# BYPASS_CAP.net
KiCad netlist of a schematic drawn in Altium Designer
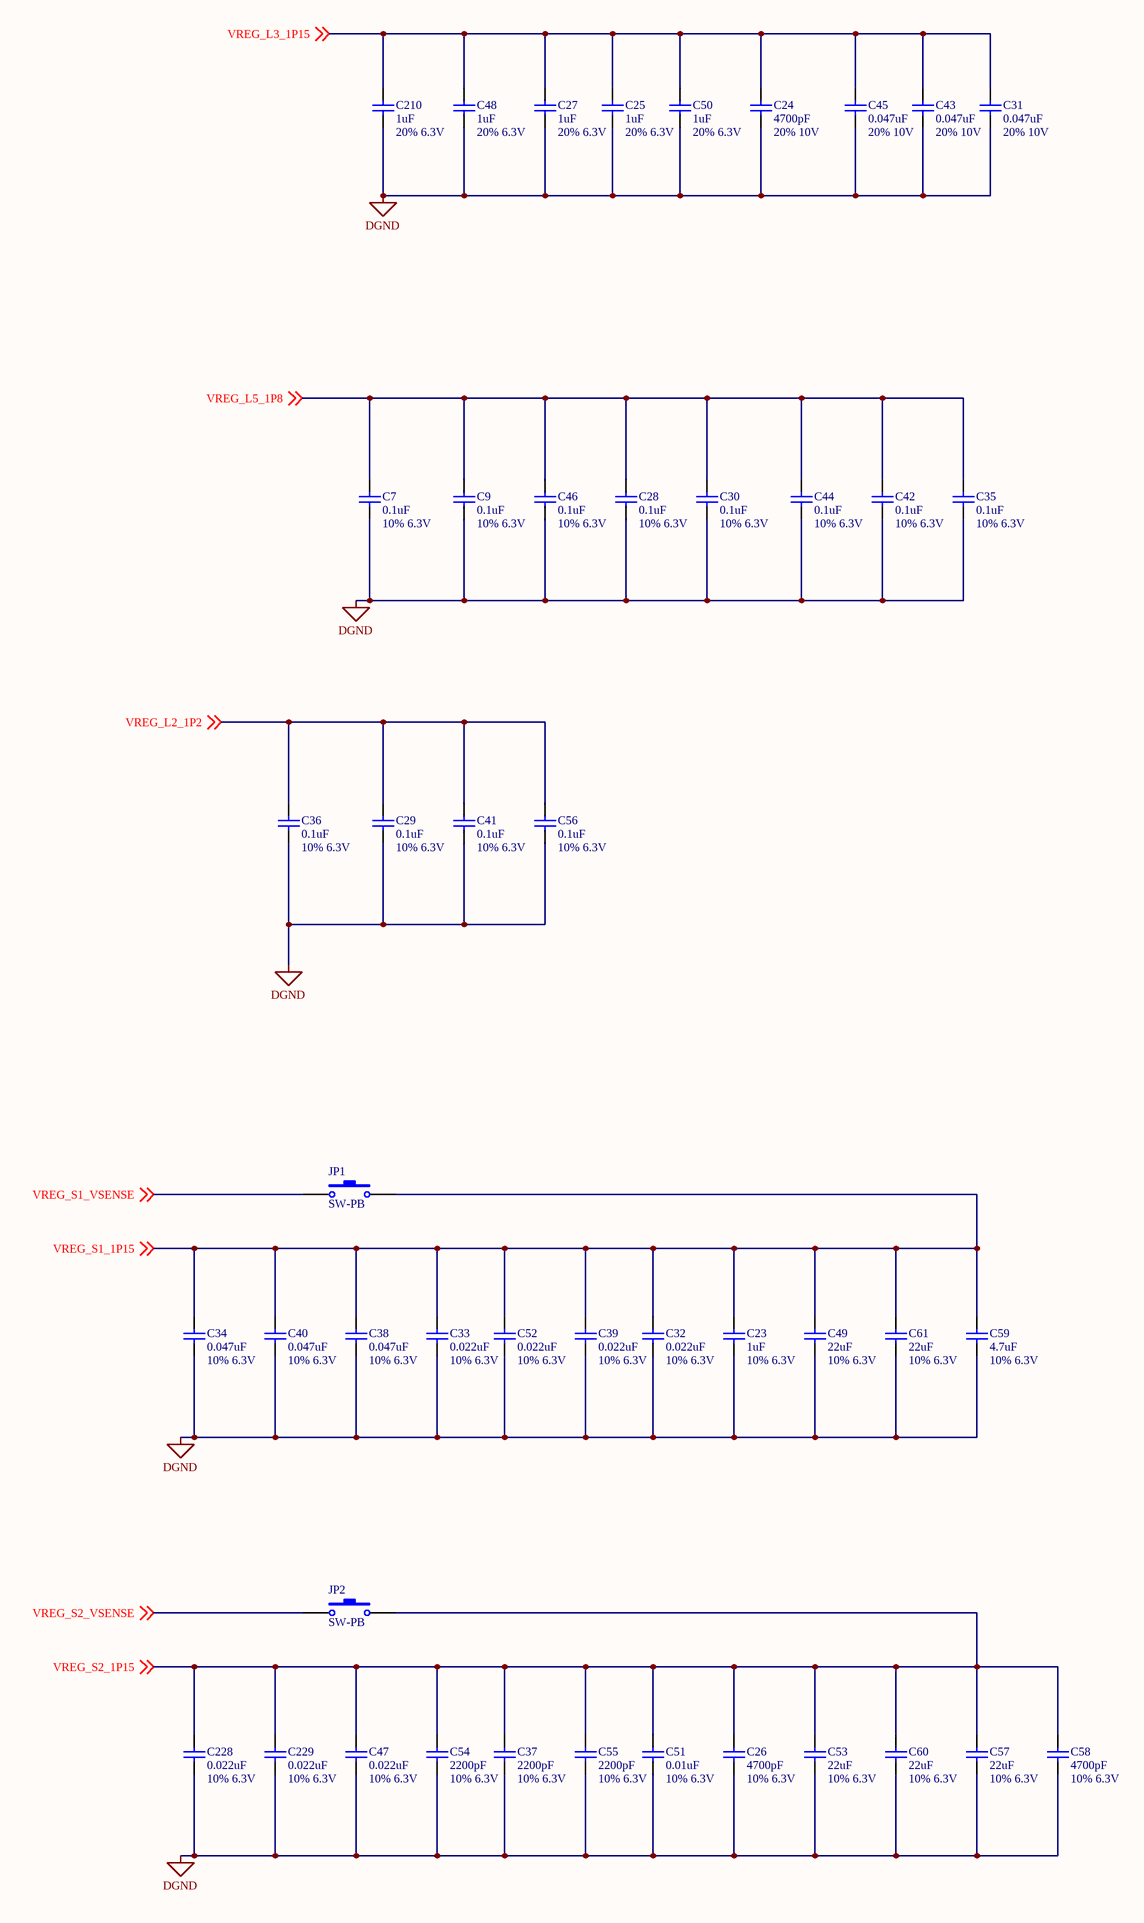
[diagram p0: BYPASS_CAP.SchDoc]

(export (version "E")
  (design (tool "Eeschema 10.0.6"))
  (components
    (comp (ref "C7")
      (value "0.1uF")
      (footprint "C0402")
      (description "Capacitor")
      (fields (field (name "ALTIUM_VALUE") "10% 6.3V") (field (name "PUBLISHER") "Altium Limited"))
      (libsource (lib "Miscellaneous Devices") (part "Cap"))
    )
    (comp (ref "C9")
      (value "0.1uF")
      (footprint "C0402")
      (description "Capacitor")
      (fields (field (name "ALTIUM_VALUE") "10% 6.3V") (field (name "PUBLISHER") "Altium Limited"))
      (libsource (lib "Miscellaneous Devices") (part "Cap"))
    )
    (comp (ref "C23")
      (value "1uF")
      (footprint "C0402")
      (description "Capacitor")
      (fields (field (name "ALTIUM_VALUE") "10% 6.3V") (field (name "PUBLISHER") "Altium Limited"))
      (libsource (lib "Miscellaneous Devices") (part "Cap"))
    )
    (comp (ref "C24")
      (value "4700pF")
      (footprint "C0402")
      (description "Capacitor")
      (fields (field (name "ALTIUM_VALUE") "20% 10V") (field (name "PUBLISHER") "Altium Limited"))
      (libsource (lib "Miscellaneous Devices") (part "Cap"))
    )
    (comp (ref "C25")
      (value "1uF")
      (footprint "C0402")
      (description "Capacitor")
      (fields (field (name "ALTIUM_VALUE") "20% 6.3V") (field (name "PUBLISHER") "Altium Limited"))
      (libsource (lib "Miscellaneous Devices") (part "Cap"))
    )
    (comp (ref "C26")
      (value "4700pF")
      (footprint "C0402")
      (description "Capacitor")
      (fields (field (name "ALTIUM_VALUE") "10% 6.3V") (field (name "PUBLISHER") "Altium Limited"))
      (libsource (lib "Miscellaneous Devices") (part "Cap"))
    )
    (comp (ref "C27")
      (value "1uF")
      (footprint "C0402")
      (description "Capacitor")
      (fields (field (name "ALTIUM_VALUE") "20% 6.3V") (field (name "PUBLISHER") "Altium Limited"))
      (libsource (lib "Miscellaneous Devices") (part "Cap"))
    )
    (comp (ref "C28")
      (value "0.1uF")
      (footprint "C0402")
      (description "Capacitor")
      (fields (field (name "ALTIUM_VALUE") "10% 6.3V") (field (name "PUBLISHER") "Altium Limited"))
      (libsource (lib "Miscellaneous Devices") (part "Cap"))
    )
    (comp (ref "C29")
      (value "0.1uF")
      (footprint "C0402")
      (description "Capacitor")
      (fields (field (name "ALTIUM_VALUE") "10% 6.3V") (field (name "PUBLISHER") "Altium Limited"))
      (libsource (lib "Miscellaneous Devices") (part "Cap"))
    )
    (comp (ref "C30")
      (value "0.1uF")
      (footprint "C0402")
      (description "Capacitor")
      (fields (field (name "ALTIUM_VALUE") "10% 6.3V") (field (name "PUBLISHER") "Altium Limited"))
      (libsource (lib "Miscellaneous Devices") (part "Cap"))
    )
    (comp (ref "C31")
      (value "0.047uF")
      (footprint "C0402")
      (description "Capacitor")
      (fields (field (name "ALTIUM_VALUE") "20% 10V") (field (name "PUBLISHER") "Altium Limited"))
      (libsource (lib "Miscellaneous Devices") (part "Cap"))
    )
    (comp (ref "C32")
      (value "0.022uF")
      (footprint "C0402")
      (description "Capacitor")
      (fields (field (name "ALTIUM_VALUE") "10% 6.3V") (field (name "PUBLISHER") "Altium Limited"))
      (libsource (lib "Miscellaneous Devices") (part "Cap"))
    )
    (comp (ref "C33")
      (value "0.022uF")
      (footprint "C0402")
      (description "Capacitor")
      (fields (field (name "ALTIUM_VALUE") "10% 6.3V") (field (name "PUBLISHER") "Altium Limited"))
      (libsource (lib "Miscellaneous Devices") (part "Cap"))
    )
    (comp (ref "C34")
      (value "0.047uF")
      (footprint "C0402")
      (description "Capacitor")
      (fields (field (name "ALTIUM_VALUE") "10% 6.3V") (field (name "PUBLISHER") "Altium Limited"))
      (libsource (lib "Miscellaneous Devices") (part "Cap"))
    )
    (comp (ref "C35")
      (value "0.1uF")
      (footprint "C0402")
      (description "Capacitor")
      (fields (field (name "ALTIUM_VALUE") "10% 6.3V") (field (name "PUBLISHER") "Altium Limited"))
      (libsource (lib "Miscellaneous Devices") (part "Cap"))
    )
    (comp (ref "C36")
      (value "0.1uF")
      (footprint "C0402")
      (description "Capacitor")
      (fields (field (name "ALTIUM_VALUE") "10% 6.3V") (field (name "PUBLISHER") "Altium Limited"))
      (libsource (lib "Miscellaneous Devices") (part "Cap"))
    )
    (comp (ref "C37")
      (value "2200pF")
      (footprint "C0402")
      (description "Capacitor")
      (fields (field (name "ALTIUM_VALUE") "10% 6.3V") (field (name "PUBLISHER") "Altium Limited"))
      (libsource (lib "Miscellaneous Devices") (part "Cap"))
    )
    (comp (ref "C38")
      (value "0.047uF")
      (footprint "C0402")
      (description "Capacitor")
      (fields (field (name "ALTIUM_VALUE") "10% 6.3V") (field (name "PUBLISHER") "Altium Limited"))
      (libsource (lib "Miscellaneous Devices") (part "Cap"))
    )
    (comp (ref "C39")
      (value "0.022uF")
      (footprint "C0402")
      (description "Capacitor")
      (fields (field (name "ALTIUM_VALUE") "10% 6.3V") (field (name "PUBLISHER") "Altium Limited"))
      (libsource (lib "Miscellaneous Devices") (part "Cap"))
    )
    (comp (ref "C40")
      (value "0.047uF")
      (footprint "C0402")
      (description "Capacitor")
      (fields (field (name "ALTIUM_VALUE") "10% 6.3V") (field (name "PUBLISHER") "Altium Limited"))
      (libsource (lib "Miscellaneous Devices") (part "Cap"))
    )
    (comp (ref "C41")
      (value "0.1uF")
      (footprint "C0402")
      (description "Capacitor")
      (fields (field (name "ALTIUM_VALUE") "10% 6.3V") (field (name "PUBLISHER") "Altium Limited"))
      (libsource (lib "Miscellaneous Devices") (part "Cap"))
    )
    (comp (ref "C42")
      (value "0.1uF")
      (footprint "C0402")
      (description "Capacitor")
      (fields (field (name "ALTIUM_VALUE") "10% 6.3V") (field (name "PUBLISHER") "Altium Limited"))
      (libsource (lib "Miscellaneous Devices") (part "Cap"))
    )
    (comp (ref "C43")
      (value "0.047uF")
      (footprint "C0402")
      (description "Capacitor")
      (fields (field (name "ALTIUM_VALUE") "20% 10V") (field (name "PUBLISHER") "Altium Limited"))
      (libsource (lib "Miscellaneous Devices") (part "Cap"))
    )
    (comp (ref "C44")
      (value "0.1uF")
      (footprint "C0402")
      (description "Capacitor")
      (fields (field (name "ALTIUM_VALUE") "10% 6.3V") (field (name "PUBLISHER") "Altium Limited"))
      (libsource (lib "Miscellaneous Devices") (part "Cap"))
    )
    (comp (ref "C45")
      (value "0.047uF")
      (footprint "C0402")
      (description "Capacitor")
      (fields (field (name "ALTIUM_VALUE") "20% 10V") (field (name "PUBLISHER") "Altium Limited"))
      (libsource (lib "Miscellaneous Devices") (part "Cap"))
    )
    (comp (ref "C46")
      (value "0.1uF")
      (footprint "C0402")
      (description "Capacitor")
      (fields (field (name "ALTIUM_VALUE") "10% 6.3V") (field (name "PUBLISHER") "Altium Limited"))
      (libsource (lib "Miscellaneous Devices") (part "Cap"))
    )
    (comp (ref "C47")
      (value "0.022uF")
      (footprint "C0402")
      (description "Capacitor")
      (fields (field (name "ALTIUM_VALUE") "10% 6.3V") (field (name "PUBLISHER") "Altium Limited"))
      (libsource (lib "Miscellaneous Devices") (part "Cap"))
    )
    (comp (ref "C48")
      (value "1uF")
      (footprint "C0402")
      (description "Capacitor")
      (fields (field (name "ALTIUM_VALUE") "20% 6.3V") (field (name "PUBLISHER") "Altium Limited"))
      (libsource (lib "Miscellaneous Devices") (part "Cap"))
    )
    (comp (ref "C49")
      (value "22uF")
      (footprint "C0402")
      (description "Capacitor")
      (fields (field (name "ALTIUM_VALUE") "10% 6.3V") (field (name "PUBLISHER") "Altium Limited"))
      (libsource (lib "Miscellaneous Devices") (part "Cap"))
    )
    (comp (ref "C50")
      (value "1uF")
      (footprint "C0402")
      (description "Capacitor")
      (fields (field (name "ALTIUM_VALUE") "20% 6.3V") (field (name "PUBLISHER") "Altium Limited"))
      (libsource (lib "Miscellaneous Devices") (part "Cap"))
    )
    (comp (ref "C51")
      (value "0.01uF")
      (footprint "C0402")
      (description "Capacitor")
      (fields (field (name "ALTIUM_VALUE") "10% 6.3V") (field (name "PUBLISHER") "Altium Limited"))
      (libsource (lib "Miscellaneous Devices") (part "Cap"))
    )
    (comp (ref "C52")
      (value "0.022uF")
      (footprint "C0402")
      (description "Capacitor")
      (fields (field (name "ALTIUM_VALUE") "10% 6.3V") (field (name "PUBLISHER") "Altium Limited"))
      (libsource (lib "Miscellaneous Devices") (part "Cap"))
    )
    (comp (ref "C53")
      (value "22uF")
      (footprint "C0402")
      (description "Capacitor")
      (fields (field (name "ALTIUM_VALUE") "10% 6.3V") (field (name "PUBLISHER") "Altium Limited"))
      (libsource (lib "Miscellaneous Devices") (part "Cap"))
    )
    (comp (ref "C54")
      (value "2200pF")
      (footprint "C0402")
      (description "Capacitor")
      (fields (field (name "ALTIUM_VALUE") "10% 6.3V") (field (name "PUBLISHER") "Altium Limited"))
      (libsource (lib "Miscellaneous Devices") (part "Cap"))
    )
    (comp (ref "C55")
      (value "2200pF")
      (footprint "C0402")
      (description "Capacitor")
      (fields (field (name "ALTIUM_VALUE") "10% 6.3V") (field (name "PUBLISHER") "Altium Limited"))
      (libsource (lib "Miscellaneous Devices") (part "Cap"))
    )
    (comp (ref "C56")
      (value "0.1uF")
      (footprint "C0402")
      (description "Capacitor")
      (fields (field (name "ALTIUM_VALUE") "10% 6.3V") (field (name "PUBLISHER") "Altium Limited"))
      (libsource (lib "Miscellaneous Devices") (part "Cap"))
    )
    (comp (ref "C57")
      (value "22uF")
      (footprint "C0402")
      (description "Capacitor")
      (fields (field (name "ALTIUM_VALUE") "10% 6.3V") (field (name "PUBLISHER") "Altium Limited"))
      (libsource (lib "Miscellaneous Devices") (part "Cap"))
    )
    (comp (ref "C58")
      (value "4700pF")
      (footprint "C0402")
      (description "Capacitor")
      (fields (field (name "ALTIUM_VALUE") "10% 6.3V") (field (name "PUBLISHER") "Altium Limited"))
      (libsource (lib "Miscellaneous Devices") (part "Cap"))
    )
    (comp (ref "C59")
      (value "4.7uF")
      (footprint "C0402")
      (description "Capacitor")
      (fields (field (name "ALTIUM_VALUE") "10% 6.3V") (field (name "PUBLISHER") "Altium Limited"))
      (libsource (lib "Miscellaneous Devices") (part "Cap"))
    )
    (comp (ref "C60")
      (value "22uF")
      (footprint "C0402")
      (description "Capacitor")
      (fields (field (name "ALTIUM_VALUE") "10% 6.3V") (field (name "PUBLISHER") "Altium Limited"))
      (libsource (lib "Miscellaneous Devices") (part "Cap"))
    )
    (comp (ref "C61")
      (value "22uF")
      (footprint "C0402")
      (description "Capacitor")
      (fields (field (name "ALTIUM_VALUE") "10% 6.3V") (field (name "PUBLISHER") "Altium Limited"))
      (libsource (lib "Miscellaneous Devices") (part "Cap"))
    )
    (comp (ref "C210")
      (value "1uF")
      (footprint "C0402")
      (description "Capacitor")
      (fields (field (name "ALTIUM_VALUE") "20% 6.3V") (field (name "PUBLISHER") "Altium Limited"))
      (libsource (lib "Miscellaneous Devices") (part "Cap"))
    )
    (comp (ref "C228")
      (value "0.022uF")
      (footprint "C0402")
      (description "Capacitor")
      (fields (field (name "ALTIUM_VALUE") "10% 6.3V") (field (name "PUBLISHER") "Altium Limited"))
      (libsource (lib "Miscellaneous Devices") (part "Cap"))
    )
    (comp (ref "C229")
      (value "0.022uF")
      (footprint "C0402")
      (description "Capacitor")
      (fields (field (name "ALTIUM_VALUE") "10% 6.3V") (field (name "PUBLISHER") "Altium Limited"))
      (libsource (lib "Miscellaneous Devices") (part "Cap"))
    )
    (comp (ref "JP1")
      (value "SW-PB")
      (footprint "SPST-2")
      (description "Switch")
      (fields (field (name "PUBLISHER") "Altium Limited"))
      (libsource (lib "Miscellaneous Devices") (part "SW-PB"))
    )
    (comp (ref "JP2")
      (value "SW-PB")
      (footprint "SPST-2")
      (description "Switch")
      (fields (field (name "PUBLISHER") "Altium Limited"))
      (libsource (lib "Miscellaneous Devices") (part "SW-PB"))
    )
  )
  (nets
    (net (code "1") (name "DGND") (class "Default")
      (node (ref "C210") (pin "1") (pinfunction "1_1") (pintype "passive"))
      (node (ref "C228") (pin "1") (pinfunction "1_1") (pintype "passive"))
      (node (ref "C229") (pin "1") (pinfunction "1_1") (pintype "passive"))
      (node (ref "C23") (pin "1") (pinfunction "1_1") (pintype "passive"))
      (node (ref "C24") (pin "1") (pinfunction "1_1") (pintype "passive"))
      (node (ref "C25") (pin "1") (pinfunction "1_1") (pintype "passive"))
      (node (ref "C26") (pin "1") (pinfunction "1_1") (pintype "passive"))
      (node (ref "C27") (pin "1") (pinfunction "1_1") (pintype "passive"))
      (node (ref "C28") (pin "1") (pinfunction "1_1") (pintype "passive"))
      (node (ref "C29") (pin "1") (pinfunction "1_1") (pintype "passive"))
      (node (ref "C30") (pin "1") (pinfunction "1_1") (pintype "passive"))
      (node (ref "C31") (pin "1") (pinfunction "1_1") (pintype "passive"))
      (node (ref "C32") (pin "1") (pinfunction "1_1") (pintype "passive"))
      (node (ref "C33") (pin "1") (pinfunction "1_1") (pintype "passive"))
      (node (ref "C34") (pin "1") (pinfunction "1_1") (pintype "passive"))
      (node (ref "C35") (pin "1") (pinfunction "1_1") (pintype "passive"))
      (node (ref "C36") (pin "1") (pinfunction "1_1") (pintype "passive"))
      (node (ref "C37") (pin "1") (pinfunction "1_1") (pintype "passive"))
      (node (ref "C38") (pin "1") (pinfunction "1_1") (pintype "passive"))
      (node (ref "C39") (pin "1") (pinfunction "1_1") (pintype "passive"))
      (node (ref "C40") (pin "1") (pinfunction "1_1") (pintype "passive"))
      (node (ref "C41") (pin "1") (pinfunction "1_1") (pintype "passive"))
      (node (ref "C42") (pin "1") (pinfunction "1_1") (pintype "passive"))
      (node (ref "C43") (pin "1") (pinfunction "1_1") (pintype "passive"))
      (node (ref "C44") (pin "1") (pinfunction "1_1") (pintype "passive"))
      (node (ref "C45") (pin "1") (pinfunction "1_1") (pintype "passive"))
      (node (ref "C46") (pin "1") (pinfunction "1_1") (pintype "passive"))
      (node (ref "C47") (pin "1") (pinfunction "1_1") (pintype "passive"))
      (node (ref "C48") (pin "1") (pinfunction "1_1") (pintype "passive"))
      (node (ref "C49") (pin "1") (pinfunction "1_1") (pintype "passive"))
      (node (ref "C50") (pin "1") (pinfunction "1_1") (pintype "passive"))
      (node (ref "C51") (pin "1") (pinfunction "1_1") (pintype "passive"))
      (node (ref "C52") (pin "1") (pinfunction "1_1") (pintype "passive"))
      (node (ref "C53") (pin "1") (pinfunction "1_1") (pintype "passive"))
      (node (ref "C54") (pin "1") (pinfunction "1_1") (pintype "passive"))
      (node (ref "C55") (pin "1") (pinfunction "1_1") (pintype "passive"))
      (node (ref "C56") (pin "1") (pinfunction "1_1") (pintype "passive"))
      (node (ref "C57") (pin "1") (pinfunction "1_1") (pintype "passive"))
      (node (ref "C58") (pin "1") (pinfunction "1_1") (pintype "passive"))
      (node (ref "C59") (pin "1") (pinfunction "1_1") (pintype "passive"))
      (node (ref "C60") (pin "1") (pinfunction "1_1") (pintype "passive"))
      (node (ref "C61") (pin "1") (pinfunction "1_1") (pintype "passive"))
      (node (ref "C7") (pin "1") (pinfunction "1_1") (pintype "passive"))
      (node (ref "C9") (pin "1") (pinfunction "1_1") (pintype "passive"))
    )
    (net (code "2") (name "VREG_L2_1P2") (class "Default")
      (node (ref "C29") (pin "2") (pinfunction "2_2") (pintype "passive"))
      (node (ref "C36") (pin "2") (pinfunction "2_2") (pintype "passive"))
      (node (ref "C41") (pin "2") (pinfunction "2_2") (pintype "passive"))
      (node (ref "C56") (pin "2") (pinfunction "2_2") (pintype "passive"))
    )
    (net (code "3") (name "VREG_L3_1P15") (class "Default")
      (node (ref "C210") (pin "2") (pinfunction "2_2") (pintype "passive"))
      (node (ref "C24") (pin "2") (pinfunction "2_2") (pintype "passive"))
      (node (ref "C25") (pin "2") (pinfunction "2_2") (pintype "passive"))
      (node (ref "C27") (pin "2") (pinfunction "2_2") (pintype "passive"))
      (node (ref "C31") (pin "2") (pinfunction "2_2") (pintype "passive"))
      (node (ref "C43") (pin "2") (pinfunction "2_2") (pintype "passive"))
      (node (ref "C45") (pin "2") (pinfunction "2_2") (pintype "passive"))
      (node (ref "C48") (pin "2") (pinfunction "2_2") (pintype "passive"))
      (node (ref "C50") (pin "2") (pinfunction "2_2") (pintype "passive"))
    )
    (net (code "4") (name "VREG_L5_1P8") (class "Default")
      (node (ref "C28") (pin "2") (pinfunction "2_2") (pintype "passive"))
      (node (ref "C30") (pin "2") (pinfunction "2_2") (pintype "passive"))
      (node (ref "C35") (pin "2") (pinfunction "2_2") (pintype "passive"))
      (node (ref "C42") (pin "2") (pinfunction "2_2") (pintype "passive"))
      (node (ref "C44") (pin "2") (pinfunction "2_2") (pintype "passive"))
      (node (ref "C46") (pin "2") (pinfunction "2_2") (pintype "passive"))
      (node (ref "C7") (pin "2") (pinfunction "2_2") (pintype "passive"))
      (node (ref "C9") (pin "2") (pinfunction "2_2") (pintype "passive"))
    )
    (net (code "5") (name "VREG_S1_1P15") (class "Default")
      (node (ref "C23") (pin "2") (pinfunction "2_2") (pintype "passive"))
      (node (ref "C32") (pin "2") (pinfunction "2_2") (pintype "passive"))
      (node (ref "C33") (pin "2") (pinfunction "2_2") (pintype "passive"))
      (node (ref "C34") (pin "2") (pinfunction "2_2") (pintype "passive"))
      (node (ref "C38") (pin "2") (pinfunction "2_2") (pintype "passive"))
      (node (ref "C39") (pin "2") (pinfunction "2_2") (pintype "passive"))
      (node (ref "C40") (pin "2") (pinfunction "2_2") (pintype "passive"))
      (node (ref "C49") (pin "2") (pinfunction "2_2") (pintype "passive"))
      (node (ref "C52") (pin "2") (pinfunction "2_2") (pintype "passive"))
      (node (ref "C59") (pin "2") (pinfunction "2_2") (pintype "passive"))
      (node (ref "C61") (pin "2") (pinfunction "2_2") (pintype "passive"))
      (node (ref "JP1") (pin "2") (pinfunction "2_2") (pintype "passive"))
    )
    (net (code "6") (name "VREG_S1_VSENSE") (class "Default")
      (node (ref "JP1") (pin "1") (pinfunction "1_1") (pintype "passive"))
    )
    (net (code "7") (name "VREG_S2_1P15") (class "Default")
      (node (ref "C228") (pin "2") (pinfunction "2_2") (pintype "passive"))
      (node (ref "C229") (pin "2") (pinfunction "2_2") (pintype "passive"))
      (node (ref "C26") (pin "2") (pinfunction "2_2") (pintype "passive"))
      (node (ref "C37") (pin "2") (pinfunction "2_2") (pintype "passive"))
      (node (ref "C47") (pin "2") (pinfunction "2_2") (pintype "passive"))
      (node (ref "C51") (pin "2") (pinfunction "2_2") (pintype "passive"))
      (node (ref "C53") (pin "2") (pinfunction "2_2") (pintype "passive"))
      (node (ref "C54") (pin "2") (pinfunction "2_2") (pintype "passive"))
      (node (ref "C55") (pin "2") (pinfunction "2_2") (pintype "passive"))
      (node (ref "C57") (pin "2") (pinfunction "2_2") (pintype "passive"))
      (node (ref "C58") (pin "2") (pinfunction "2_2") (pintype "passive"))
      (node (ref "C60") (pin "2") (pinfunction "2_2") (pintype "passive"))
      (node (ref "JP2") (pin "2") (pinfunction "2_2") (pintype "passive"))
    )
    (net (code "8") (name "VREG_S2_VSENSE") (class "Default")
      (node (ref "JP2") (pin "1") (pinfunction "1_1") (pintype "passive"))
    )
  )
)
